# board.net
KiCad netlist of a schematic drawn in EAGLE
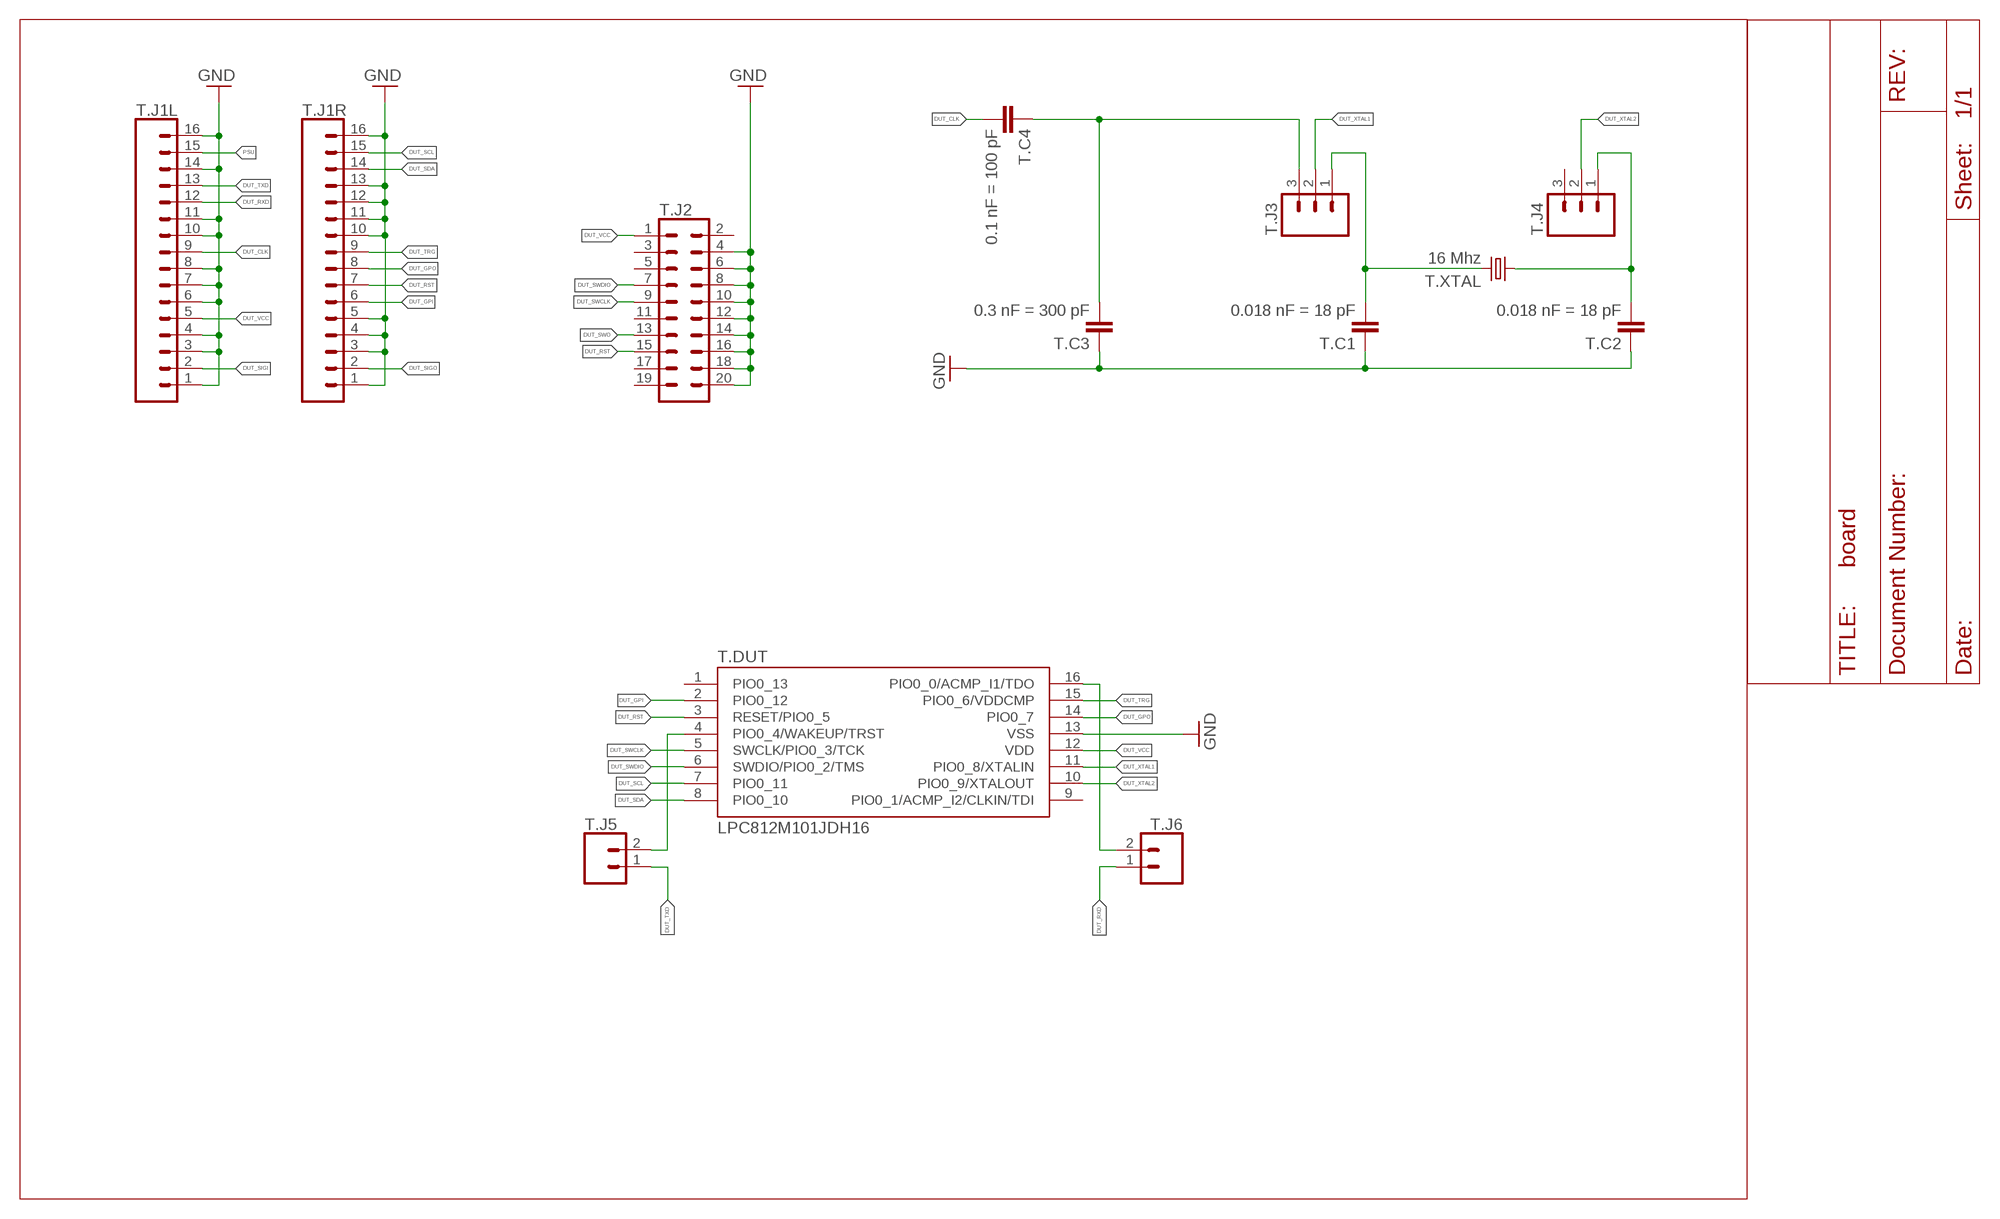
[diagram p0: schematic, sheet 1]

(export (version "E")
  (design (tool "Eeschema 10.0.6"))
  (components
    (comp (ref "T.C1")
      (value "0.018 nF = 18 pF")
      (footprint "eagle-import:0603-CAP")
      (libsource (lib "eagle-import") (part "CAP0603-CAP"))
    )
    (comp (ref "T.C2")
      (value "0.018 nF = 18 pF")
      (footprint "eagle-import:0603-CAP")
      (libsource (lib "eagle-import") (part "CAP0603-CAP"))
    )
    (comp (ref "T.C3")
      (value "0.3 nF = 300 pF")
      (footprint "eagle-import:0603-CAP")
      (libsource (lib "eagle-import") (part "CAP0603-CAP"))
    )
    (comp (ref "T.C4")
      (value "0.1 nF = 100 pF")
      (footprint "eagle-import:0603-CAP")
      (libsource (lib "eagle-import") (part "CAP0603-CAP"))
    )
    (comp (ref "T.DUT")
      (value "LPC812M101JDH16")
      (footprint "eagle-import:TSSOP16")
      (libsource (lib "eagle-import") (part "LPC812M101JDH16"))
    )
    (comp (ref "T.J1L")
      (value "CONN_16")
      (footprint "eagle-import:1X16")
      (libsource (lib "eagle-import") (part "CONN_16"))
    )
    (comp (ref "T.J1R")
      (value "CONN_16")
      (footprint "eagle-import:1X16")
      (libsource (lib "eagle-import") (part "CONN_16"))
    )
    (comp (ref "T.J2")
      (value "CONN_10X2")
      (footprint "eagle-import:2X10")
      (libsource (lib "eagle-import") (part "CONN_10X2"))
    )
    (comp (ref "T.J3")
      (value "M03PTH")
      (footprint "eagle-import:1X03")
      (libsource (lib "eagle-import") (part "M03PTH"))
    )
    (comp (ref "T.J4")
      (value "M03PTH")
      (footprint "eagle-import:1X03")
      (libsource (lib "eagle-import") (part "M03PTH"))
    )
    (comp (ref "T.J5")
      (value "CONN_02")
      (footprint "eagle-import:1X02")
      (libsource (lib "eagle-import") (part "CONN_02"))
    )
    (comp (ref "T.J6")
      (value "CONN_02")
      (footprint "eagle-import:1X02")
      (libsource (lib "eagle-import") (part "CONN_02"))
    )
    (comp (ref "T.XTAL")
      (value "16 Mhz")
      (footprint "eagle-import:HC49US")
      (libsource (lib "eagle-import") (part "CRYSTALHC49US"))
    )
  )
  (nets
    (net (code "1") (name "DUT_CLK") (class "Default")
      (node (ref "T.C4") (pin "2") (pinfunction "2_2") (pintype "passive"))
      (node (ref "T.J1L") (pin "9") (pinfunction "9_9") (pintype "passive"))
    )
    (net (code "2") (name "DUT_GPI") (class "Default")
      (node (ref "T.DUT") (pin "2") (pinfunction "PIO0_12_2") (pintype "bidirectional"))
      (node (ref "T.J1R") (pin "6") (pinfunction "6_6") (pintype "passive"))
    )
    (net (code "3") (name "DUT_GPO") (class "Default")
      (node (ref "T.DUT") (pin "14") (pinfunction "PIO0_7_14") (pintype "bidirectional"))
      (node (ref "T.J1R") (pin "8") (pinfunction "8_8") (pintype "passive"))
    )
    (net (code "4") (name "DUT_RST") (class "Default")
      (node (ref "T.DUT") (pin "3") (pinfunction "RESET/PIO0_5_3") (pintype "bidirectional"))
      (node (ref "T.J1R") (pin "7") (pinfunction "7_7") (pintype "passive"))
      (node (ref "T.J2") (pin "15") (pinfunction "15_15") (pintype "passive"))
    )
    (net (code "5") (name "DUT_RXD") (class "Default")
      (node (ref "T.J1L") (pin "12") (pinfunction "12_12") (pintype "passive"))
      (node (ref "T.J6") (pin "1") (pinfunction "1_1") (pintype "passive"))
    )
    (net (code "6") (name "DUT_SCL") (class "Default")
      (node (ref "T.DUT") (pin "7") (pinfunction "PIO0_11_7") (pintype "bidirectional"))
      (node (ref "T.J1R") (pin "15") (pinfunction "15_15") (pintype "passive"))
    )
    (net (code "7") (name "DUT_SDA") (class "Default")
      (node (ref "T.DUT") (pin "8") (pinfunction "PIO0_10_8") (pintype "bidirectional"))
      (node (ref "T.J1R") (pin "14") (pinfunction "14_14") (pintype "passive"))
    )
    (net (code "8") (name "DUT_SIGI") (class "Default")
      (node (ref "T.J1L") (pin "2") (pinfunction "2_2") (pintype "passive"))
    )
    (net (code "9") (name "DUT_SIGO") (class "Default")
      (node (ref "T.J1R") (pin "2") (pinfunction "2_2") (pintype "passive"))
    )
    (net (code "10") (name "DUT_SWCLK") (class "Default")
      (node (ref "T.DUT") (pin "5") (pinfunction "SWCLK/PIO0_3/TCK_5") (pintype "bidirectional"))
      (node (ref "T.J2") (pin "9") (pinfunction "9_9") (pintype "passive"))
    )
    (net (code "11") (name "DUT_SWDIO") (class "Default")
      (node (ref "T.DUT") (pin "6") (pinfunction "SWDIO/PIO0_2/TMS_6") (pintype "bidirectional"))
      (node (ref "T.J2") (pin "7") (pinfunction "7_7") (pintype "passive"))
    )
    (net (code "12") (name "DUT_SWO") (class "Default")
      (node (ref "T.J2") (pin "13") (pinfunction "13_13") (pintype "passive"))
    )
    (net (code "13") (name "DUT_TRG") (class "Default")
      (node (ref "T.DUT") (pin "15") (pinfunction "PIO0_6/VDDCMP_15") (pintype "bidirectional"))
      (node (ref "T.J1R") (pin "9") (pinfunction "9_9") (pintype "passive"))
    )
    (net (code "14") (name "DUT_TXD") (class "Default")
      (node (ref "T.J1L") (pin "13") (pinfunction "13_13") (pintype "passive"))
      (node (ref "T.J5") (pin "1") (pinfunction "1_1") (pintype "passive"))
    )
    (net (code "15") (name "DUT_VCC") (class "Default")
      (node (ref "T.DUT") (pin "12") (pinfunction "VDD_12") (pintype "bidirectional"))
      (node (ref "T.J1L") (pin "5") (pinfunction "5_5") (pintype "passive"))
      (node (ref "T.J2") (pin "1") (pinfunction "1_1") (pintype "passive"))
    )
    (net (code "16") (name "DUT_XTAL1") (class "Default")
      (node (ref "T.DUT") (pin "11") (pinfunction "PIO0_8/XTALIN_11") (pintype "bidirectional"))
      (node (ref "T.J3") (pin "2") (pinfunction "2_2") (pintype "passive"))
    )
    (net (code "17") (name "DUT_XTAL2") (class "Default")
      (node (ref "T.DUT") (pin "10") (pinfunction "PIO0_9/XTALOUT_10") (pintype "bidirectional"))
      (node (ref "T.J4") (pin "2") (pinfunction "2_2") (pintype "passive"))
    )
    (net (code "18") (name "GND") (class "Default")
      (node (ref "T.C1") (pin "1") (pinfunction "1_1") (pintype "passive"))
      (node (ref "T.C2") (pin "1") (pinfunction "1_1") (pintype "passive"))
      (node (ref "T.C3") (pin "1") (pinfunction "1_1") (pintype "passive"))
      (node (ref "T.DUT") (pin "13") (pinfunction "VSS_13") (pintype "bidirectional"))
      (node (ref "T.J1L") (pin "1") (pinfunction "1_1") (pintype "passive"))
      (node (ref "T.J1L") (pin "10") (pinfunction "10_10") (pintype "passive"))
      (node (ref "T.J1L") (pin "11") (pinfunction "11_11") (pintype "passive"))
      (node (ref "T.J1L") (pin "14") (pinfunction "14_14") (pintype "passive"))
      (node (ref "T.J1L") (pin "16") (pinfunction "16_16") (pintype "passive"))
      (node (ref "T.J1L") (pin "3") (pinfunction "3_3") (pintype "passive"))
      (node (ref "T.J1L") (pin "4") (pinfunction "4_4") (pintype "passive"))
      (node (ref "T.J1L") (pin "6") (pinfunction "6_6") (pintype "passive"))
      (node (ref "T.J1L") (pin "7") (pinfunction "7_7") (pintype "passive"))
      (node (ref "T.J1L") (pin "8") (pinfunction "8_8") (pintype "passive"))
      (node (ref "T.J1R") (pin "1") (pinfunction "1_1") (pintype "passive"))
      (node (ref "T.J1R") (pin "10") (pinfunction "10_10") (pintype "passive"))
      (node (ref "T.J1R") (pin "11") (pinfunction "11_11") (pintype "passive"))
      (node (ref "T.J1R") (pin "12") (pinfunction "12_12") (pintype "passive"))
      (node (ref "T.J1R") (pin "13") (pinfunction "13_13") (pintype "passive"))
      (node (ref "T.J1R") (pin "16") (pinfunction "16_16") (pintype "passive"))
      (node (ref "T.J1R") (pin "3") (pinfunction "3_3") (pintype "passive"))
      (node (ref "T.J1R") (pin "4") (pinfunction "4_4") (pintype "passive"))
      (node (ref "T.J1R") (pin "5") (pinfunction "5_5") (pintype "passive"))
      (node (ref "T.J2") (pin "10") (pinfunction "10_10") (pintype "passive"))
      (node (ref "T.J2") (pin "12") (pinfunction "12_12") (pintype "passive"))
      (node (ref "T.J2") (pin "14") (pinfunction "14_14") (pintype "passive"))
      (node (ref "T.J2") (pin "16") (pinfunction "16_16") (pintype "passive"))
      (node (ref "T.J2") (pin "18") (pinfunction "18_18") (pintype "passive"))
      (node (ref "T.J2") (pin "20") (pinfunction "20_20") (pintype "passive"))
      (node (ref "T.J2") (pin "4") (pinfunction "4_4") (pintype "passive"))
      (node (ref "T.J2") (pin "6") (pinfunction "6_6") (pintype "passive"))
      (node (ref "T.J2") (pin "8") (pinfunction "8_8") (pintype "passive"))
    )
    (net (code "19") (name "Net-(T.C1-Pad2)") (class "Default")
      (node (ref "T.C1") (pin "2") (pinfunction "2_2") (pintype "passive"))
      (node (ref "T.J3") (pin "1") (pinfunction "1_1") (pintype "passive"))
      (node (ref "T.XTAL") (pin "2") (pinfunction "2_2") (pintype "passive"))
    )
    (net (code "20") (name "Net-(T.C2-Pad2)") (class "Default")
      (node (ref "T.C2") (pin "2") (pinfunction "2_2") (pintype "passive"))
      (node (ref "T.J4") (pin "1") (pinfunction "1_1") (pintype "passive"))
      (node (ref "T.XTAL") (pin "1") (pinfunction "1_1") (pintype "passive"))
    )
    (net (code "21") (name "Net-(T.C3-Pad2)") (class "Default")
      (node (ref "T.C3") (pin "2") (pinfunction "2_2") (pintype "passive"))
      (node (ref "T.C4") (pin "1") (pinfunction "1_1") (pintype "passive"))
      (node (ref "T.J3") (pin "3") (pinfunction "3_3") (pintype "passive"))
    )
    (net (code "22") (name "Net-(T.DUT-PIO0_0{slash}ACMP_I1{slash}TDO)") (class "Default")
      (node (ref "T.DUT") (pin "16") (pinfunction "PIO0_0/ACMP_I1/TDO_16") (pintype "bidirectional"))
      (node (ref "T.J6") (pin "2") (pinfunction "2_2") (pintype "passive"))
    )
    (net (code "23") (name "Net-(T.DUT-PIO0_4{slash}WAKEUP{slash}TRST)") (class "Default")
      (node (ref "T.DUT") (pin "4") (pinfunction "PIO0_4/WAKEUP/TRST_4") (pintype "bidirectional"))
      (node (ref "T.J5") (pin "2") (pinfunction "2_2") (pintype "passive"))
    )
    (net (code "24") (name "PSU") (class "Default")
      (node (ref "T.J1L") (pin "15") (pinfunction "15_15") (pintype "passive"))
    )
    (net (code "25") (name "unconnected-(T.DUT-PIO0_1{slash}ACMP_I2{slash}CLKIN{slash}TDI-Pad9)") (class "Default")
      (node (ref "T.DUT") (pin "9") (pinfunction "PIO0_1/ACMP_I2/CLKIN/TDI_9") (pintype "bidirectional"))
    )
    (net (code "26") (name "unconnected-(T.DUT-PIO0_13-Pad1)") (class "Default")
      (node (ref "T.DUT") (pin "1") (pinfunction "PIO0_13_1") (pintype "bidirectional"))
    )
    (net (code "27") (name "unconnected-(T.J2-Pad2)") (class "Default")
      (node (ref "T.J2") (pin "2") (pinfunction "2_2") (pintype "passive"))
    )
    (net (code "28") (name "unconnected-(T.J2-Pad3)") (class "Default")
      (node (ref "T.J2") (pin "3") (pinfunction "3_3") (pintype "passive"))
    )
    (net (code "29") (name "unconnected-(T.J2-Pad5)") (class "Default")
      (node (ref "T.J2") (pin "5") (pinfunction "5_5") (pintype "passive"))
    )
    (net (code "30") (name "unconnected-(T.J2-Pad11)") (class "Default")
      (node (ref "T.J2") (pin "11") (pinfunction "11_11") (pintype "passive"))
    )
    (net (code "31") (name "unconnected-(T.J2-Pad17)") (class "Default")
      (node (ref "T.J2") (pin "17") (pinfunction "17_17") (pintype "passive"))
    )
    (net (code "32") (name "unconnected-(T.J2-Pad19)") (class "Default")
      (node (ref "T.J2") (pin "19") (pinfunction "19_19") (pintype "passive"))
    )
    (net (code "33") (name "unconnected-(T.J4-Pad3)") (class "Default")
      (node (ref "T.J4") (pin "3") (pinfunction "3_3") (pintype "passive"))
    )
  )
)
